# hex-motor-controler.net
KiCad netlist of a schematic drawn in EAGLE
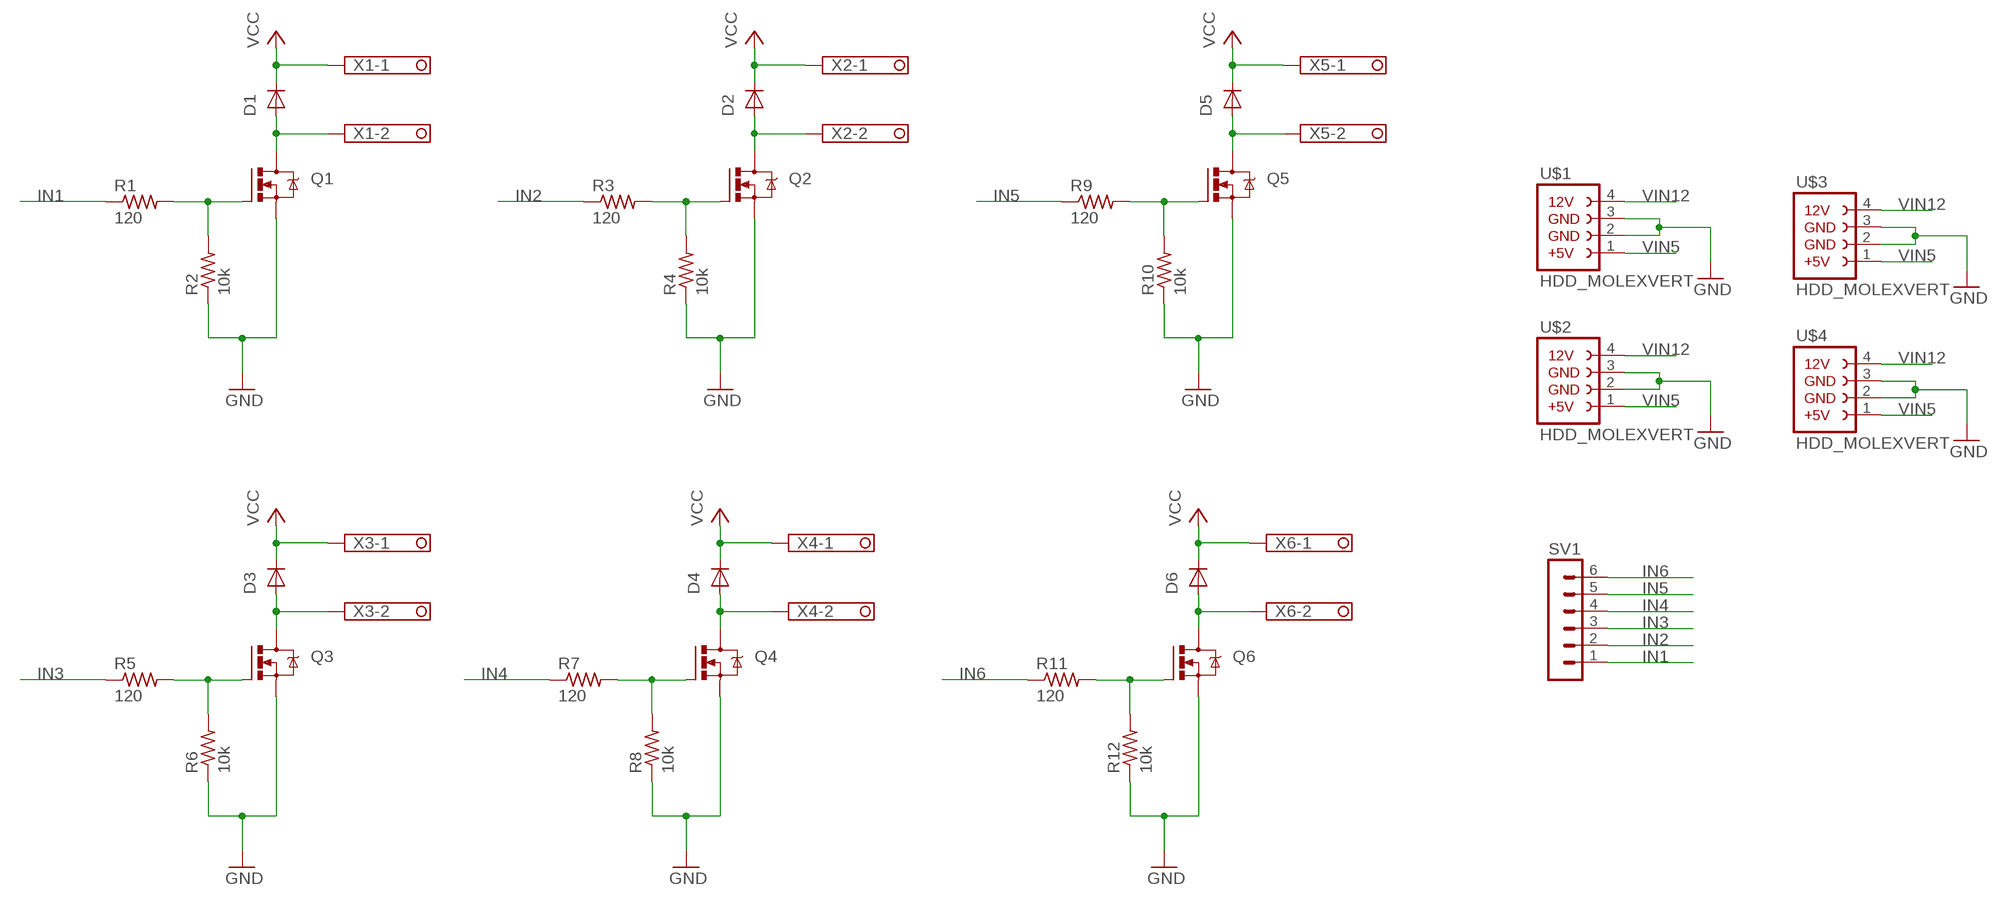
[diagram p0: schematic, sheet 1]

(export (version "E")
  (design (tool "Eeschema 10.0.6"))
  (components
    (comp (ref "D1")
      (value "1N4004")
      (footprint "eagle-import:DO41-10")
      (libsource (lib "eagle-import") (part "1N4004"))
    )
    (comp (ref "D2")
      (value "1N4004")
      (footprint "eagle-import:DO41-10")
      (libsource (lib "eagle-import") (part "1N4004"))
    )
    (comp (ref "D3")
      (value "1N4004")
      (footprint "eagle-import:DO41-10")
      (libsource (lib "eagle-import") (part "1N4004"))
    )
    (comp (ref "D4")
      (value "1N4004")
      (footprint "eagle-import:DO41-10")
      (libsource (lib "eagle-import") (part "1N4004"))
    )
    (comp (ref "D5")
      (value "1N4004")
      (footprint "eagle-import:DO41-10")
      (libsource (lib "eagle-import") (part "1N4004"))
    )
    (comp (ref "D6")
      (value "1N4004")
      (footprint "eagle-import:DO41-10")
      (libsource (lib "eagle-import") (part "1N4004"))
    )
    (comp (ref "Q1")
      (value "IRF530")
      (footprint "eagle-import:TO220BV")
      (libsource (lib "eagle-import") (part "IRF530"))
    )
    (comp (ref "Q2")
      (value "IRF530")
      (footprint "eagle-import:TO220BV")
      (libsource (lib "eagle-import") (part "IRF530"))
    )
    (comp (ref "Q3")
      (value "IRF530")
      (footprint "eagle-import:TO220BV")
      (libsource (lib "eagle-import") (part "IRF530"))
    )
    (comp (ref "Q4")
      (value "IRF530")
      (footprint "eagle-import:TO220BV")
      (libsource (lib "eagle-import") (part "IRF530"))
    )
    (comp (ref "Q5")
      (value "IRF530")
      (footprint "eagle-import:TO220BV")
      (libsource (lib "eagle-import") (part "IRF530"))
    )
    (comp (ref "Q6")
      (value "IRF530")
      (footprint "eagle-import:TO220BV")
      (libsource (lib "eagle-import") (part "IRF530"))
    )
    (comp (ref "R1")
      (value "120")
      (footprint "eagle-import:0207_7")
      (libsource (lib "eagle-import") (part "R-US_0207/7"))
    )
    (comp (ref "R2")
      (value "10k")
      (footprint "eagle-import:0207_7")
      (libsource (lib "eagle-import") (part "R-US_0207/7"))
    )
    (comp (ref "R3")
      (value "120")
      (footprint "eagle-import:0207_7")
      (libsource (lib "eagle-import") (part "R-US_0207/7"))
    )
    (comp (ref "R4")
      (value "10k")
      (footprint "eagle-import:0207_7")
      (libsource (lib "eagle-import") (part "R-US_0207/7"))
    )
    (comp (ref "R5")
      (value "120")
      (footprint "eagle-import:0207_7")
      (libsource (lib "eagle-import") (part "R-US_0207/7"))
    )
    (comp (ref "R6")
      (value "10k")
      (footprint "eagle-import:0207_7")
      (libsource (lib "eagle-import") (part "R-US_0207/7"))
    )
    (comp (ref "R7")
      (value "120")
      (footprint "eagle-import:0207_7")
      (libsource (lib "eagle-import") (part "R-US_0207/7"))
    )
    (comp (ref "R8")
      (value "10k")
      (footprint "eagle-import:0207_7")
      (libsource (lib "eagle-import") (part "R-US_0207/7"))
    )
    (comp (ref "R9")
      (value "120")
      (footprint "eagle-import:0207_7")
      (libsource (lib "eagle-import") (part "R-US_0207/7"))
    )
    (comp (ref "R10")
      (value "10k")
      (footprint "eagle-import:0207_7")
      (libsource (lib "eagle-import") (part "R-US_0207/7"))
    )
    (comp (ref "R11")
      (value "120")
      (footprint "eagle-import:0207_7")
      (libsource (lib "eagle-import") (part "R-US_0207/7"))
    )
    (comp (ref "R12")
      (value "10k")
      (footprint "eagle-import:0207_7")
      (libsource (lib "eagle-import") (part "R-US_0207/7"))
    )
    (comp (ref "SV1")
      (value "MA06-1")
      (footprint "eagle-import:MA06-1")
      (libsource (lib "eagle-import") (part "MA06-1"))
    )
    (comp (ref "U$1")
      (value "HDD_MOLEXVERT")
      (footprint "eagle-import:HDD_MOLEX_VERT")
      (libsource (lib "eagle-import") (part "HDD_MOLEXVERT"))
    )
    (comp (ref "U$2")
      (value "HDD_MOLEXVERT")
      (footprint "eagle-import:HDD_MOLEX_VERT")
      (libsource (lib "eagle-import") (part "HDD_MOLEXVERT"))
    )
    (comp (ref "U$3")
      (value "HDD_MOLEXVERT")
      (footprint "eagle-import:HDD_MOLEX_VERT")
      (libsource (lib "eagle-import") (part "HDD_MOLEXVERT"))
    )
    (comp (ref "U$4")
      (value "HDD_MOLEXVERT")
      (footprint "eagle-import:HDD_MOLEX_VERT")
      (libsource (lib "eagle-import") (part "HDD_MOLEXVERT"))
    )
    (comp (ref "X1")
      (value "1751248")
      (footprint "eagle-import:1751248")
      (libsource (lib "eagle-import") (part "1751248"))
    )
    (comp (ref "X2")
      (value "1751248")
      (footprint "eagle-import:1751248")
      (libsource (lib "eagle-import") (part "1751248"))
    )
    (comp (ref "X3")
      (value "1751248")
      (footprint "eagle-import:1751248")
      (libsource (lib "eagle-import") (part "1751248"))
    )
    (comp (ref "X4")
      (value "1751248")
      (footprint "eagle-import:1751248")
      (libsource (lib "eagle-import") (part "1751248"))
    )
    (comp (ref "X5")
      (value "1751248")
      (footprint "eagle-import:1751248")
      (libsource (lib "eagle-import") (part "1751248"))
    )
    (comp (ref "X6")
      (value "1751248")
      (footprint "eagle-import:1751248")
      (libsource (lib "eagle-import") (part "1751248"))
    )
  )
  (nets
    (net (code "1") (name "/IN1") (class "Default")
      (node (ref "R1") (pin "1") (pinfunction "1_1") (pintype "passive"))
      (node (ref "SV1") (pin "1") (pinfunction "1_1") (pintype "passive"))
    )
    (net (code "2") (name "/IN2") (class "Default")
      (node (ref "R3") (pin "1") (pinfunction "1_1") (pintype "passive"))
      (node (ref "SV1") (pin "2") (pinfunction "2_2") (pintype "passive"))
    )
    (net (code "3") (name "/IN3") (class "Default")
      (node (ref "R5") (pin "1") (pinfunction "1_1") (pintype "passive"))
      (node (ref "SV1") (pin "3") (pinfunction "3_3") (pintype "passive"))
    )
    (net (code "4") (name "/IN4") (class "Default")
      (node (ref "R7") (pin "1") (pinfunction "1_1") (pintype "passive"))
      (node (ref "SV1") (pin "4") (pinfunction "4_4") (pintype "passive"))
    )
    (net (code "5") (name "/IN5") (class "Default")
      (node (ref "R9") (pin "1") (pinfunction "1_1") (pintype "passive"))
      (node (ref "SV1") (pin "5") (pinfunction "5_5") (pintype "passive"))
    )
    (net (code "6") (name "/IN6") (class "Default")
      (node (ref "R11") (pin "1") (pinfunction "1_1") (pintype "passive"))
      (node (ref "SV1") (pin "6") (pinfunction "6_6") (pintype "passive"))
    )
    (net (code "7") (name "/VIN5") (class "Default")
      (node (ref "U$1") (pin "1") (pinfunction "4_1") (pintype "passive"))
      (node (ref "U$2") (pin "1") (pinfunction "4_1") (pintype "passive"))
      (node (ref "U$3") (pin "1") (pinfunction "4_1") (pintype "passive"))
      (node (ref "U$4") (pin "1") (pinfunction "4_1") (pintype "passive"))
    )
    (net (code "8") (name "/VIN12") (class "Default")
      (node (ref "U$1") (pin "4") (pinfunction "1_4") (pintype "passive"))
      (node (ref "U$2") (pin "4") (pinfunction "1_4") (pintype "passive"))
      (node (ref "U$3") (pin "4") (pinfunction "1_4") (pintype "passive"))
      (node (ref "U$4") (pin "4") (pinfunction "1_4") (pintype "passive"))
    )
    (net (code "9") (name "GND") (class "Default")
      (node (ref "Q1") (pin "S") (pinfunction "S_S") (pintype "passive"))
      (node (ref "Q2") (pin "S") (pinfunction "S_S") (pintype "passive"))
      (node (ref "Q3") (pin "S") (pinfunction "S_S") (pintype "passive"))
      (node (ref "Q4") (pin "S") (pinfunction "S_S") (pintype "passive"))
      (node (ref "Q5") (pin "S") (pinfunction "S_S") (pintype "passive"))
      (node (ref "Q6") (pin "S") (pinfunction "S_S") (pintype "passive"))
      (node (ref "R10") (pin "1") (pinfunction "1_1") (pintype "passive"))
      (node (ref "R12") (pin "1") (pinfunction "1_1") (pintype "passive"))
      (node (ref "R2") (pin "1") (pinfunction "1_1") (pintype "passive"))
      (node (ref "R4") (pin "1") (pinfunction "1_1") (pintype "passive"))
      (node (ref "R6") (pin "1") (pinfunction "1_1") (pintype "passive"))
      (node (ref "R8") (pin "1") (pinfunction "1_1") (pintype "passive"))
      (node (ref "U$1") (pin "2") (pinfunction "3_2") (pintype "passive"))
      (node (ref "U$1") (pin "3") (pinfunction "2_3") (pintype "passive"))
      (node (ref "U$2") (pin "2") (pinfunction "3_2") (pintype "passive"))
      (node (ref "U$2") (pin "3") (pinfunction "2_3") (pintype "passive"))
      (node (ref "U$3") (pin "2") (pinfunction "3_2") (pintype "passive"))
      (node (ref "U$3") (pin "3") (pinfunction "2_3") (pintype "passive"))
      (node (ref "U$4") (pin "2") (pinfunction "3_2") (pintype "passive"))
      (node (ref "U$4") (pin "3") (pinfunction "2_3") (pintype "passive"))
    )
    (net (code "10") (name "Net-(Q1-PadG)") (class "Default")
      (node (ref "Q1") (pin "G") (pinfunction "G_G") (pintype "passive"))
      (node (ref "R1") (pin "2") (pinfunction "2_2") (pintype "passive"))
      (node (ref "R2") (pin "2") (pinfunction "2_2") (pintype "passive"))
    )
    (net (code "11") (name "Net-(Q2-PadG)") (class "Default")
      (node (ref "Q2") (pin "G") (pinfunction "G_G") (pintype "passive"))
      (node (ref "R3") (pin "2") (pinfunction "2_2") (pintype "passive"))
      (node (ref "R4") (pin "2") (pinfunction "2_2") (pintype "passive"))
    )
    (net (code "12") (name "Net-(Q3-PadG)") (class "Default")
      (node (ref "Q3") (pin "G") (pinfunction "G_G") (pintype "passive"))
      (node (ref "R5") (pin "2") (pinfunction "2_2") (pintype "passive"))
      (node (ref "R6") (pin "2") (pinfunction "2_2") (pintype "passive"))
    )
    (net (code "13") (name "Net-(Q4-PadG)") (class "Default")
      (node (ref "Q4") (pin "G") (pinfunction "G_G") (pintype "passive"))
      (node (ref "R7") (pin "2") (pinfunction "2_2") (pintype "passive"))
      (node (ref "R8") (pin "2") (pinfunction "2_2") (pintype "passive"))
    )
    (net (code "14") (name "Net-(Q5-PadG)") (class "Default")
      (node (ref "Q5") (pin "G") (pinfunction "G_G") (pintype "passive"))
      (node (ref "R10") (pin "2") (pinfunction "2_2") (pintype "passive"))
      (node (ref "R9") (pin "2") (pinfunction "2_2") (pintype "passive"))
    )
    (net (code "15") (name "Net-(Q6-PadG)") (class "Default")
      (node (ref "Q6") (pin "G") (pinfunction "G_G") (pintype "passive"))
      (node (ref "R11") (pin "2") (pinfunction "2_2") (pintype "passive"))
      (node (ref "R12") (pin "2") (pinfunction "2_2") (pintype "passive"))
    )
    (net (code "16") (name "Net-(X1B-K)") (class "Default")
      (node (ref "D1") (pin "A") (pinfunction "A_A") (pintype "passive"))
      (node (ref "Q1") (pin "D") (pinfunction "D_D") (pintype "passive"))
      (node (ref "X1") (pin "2") (pinfunction "K_2") (pintype "passive"))
    )
    (net (code "17") (name "Net-(X2B-K)") (class "Default")
      (node (ref "D2") (pin "A") (pinfunction "A_A") (pintype "passive"))
      (node (ref "Q2") (pin "D") (pinfunction "D_D") (pintype "passive"))
      (node (ref "X2") (pin "2") (pinfunction "K_2") (pintype "passive"))
    )
    (net (code "18") (name "Net-(X3B-K)") (class "Default")
      (node (ref "D3") (pin "A") (pinfunction "A_A") (pintype "passive"))
      (node (ref "Q3") (pin "D") (pinfunction "D_D") (pintype "passive"))
      (node (ref "X3") (pin "2") (pinfunction "K_2") (pintype "passive"))
    )
    (net (code "19") (name "Net-(X4B-K)") (class "Default")
      (node (ref "D4") (pin "A") (pinfunction "A_A") (pintype "passive"))
      (node (ref "Q4") (pin "D") (pinfunction "D_D") (pintype "passive"))
      (node (ref "X4") (pin "2") (pinfunction "K_2") (pintype "passive"))
    )
    (net (code "20") (name "Net-(X5B-K)") (class "Default")
      (node (ref "D5") (pin "A") (pinfunction "A_A") (pintype "passive"))
      (node (ref "Q5") (pin "D") (pinfunction "D_D") (pintype "passive"))
      (node (ref "X5") (pin "2") (pinfunction "K_2") (pintype "passive"))
    )
    (net (code "21") (name "Net-(X6B-K)") (class "Default")
      (node (ref "D6") (pin "A") (pinfunction "A_A") (pintype "passive"))
      (node (ref "Q6") (pin "D") (pinfunction "D_D") (pintype "passive"))
      (node (ref "X6") (pin "2") (pinfunction "K_2") (pintype "passive"))
    )
    (net (code "22") (name "VCC") (class "Default")
      (node (ref "D1") (pin "C") (pinfunction "C_C") (pintype "passive"))
      (node (ref "D2") (pin "C") (pinfunction "C_C") (pintype "passive"))
      (node (ref "D3") (pin "C") (pinfunction "C_C") (pintype "passive"))
      (node (ref "D4") (pin "C") (pinfunction "C_C") (pintype "passive"))
      (node (ref "D5") (pin "C") (pinfunction "C_C") (pintype "passive"))
      (node (ref "D6") (pin "C") (pinfunction "C_C") (pintype "passive"))
      (node (ref "X1") (pin "1") (pinfunction "K_1") (pintype "passive"))
      (node (ref "X2") (pin "1") (pinfunction "K_1") (pintype "passive"))
      (node (ref "X3") (pin "1") (pinfunction "K_1") (pintype "passive"))
      (node (ref "X4") (pin "1") (pinfunction "K_1") (pintype "passive"))
      (node (ref "X5") (pin "1") (pinfunction "K_1") (pintype "passive"))
      (node (ref "X6") (pin "1") (pinfunction "K_1") (pintype "passive"))
    )
  )
)
